# Terminierung_RS485_RJ45.net
KiCad netlist of a schematic drawn in EAGLE
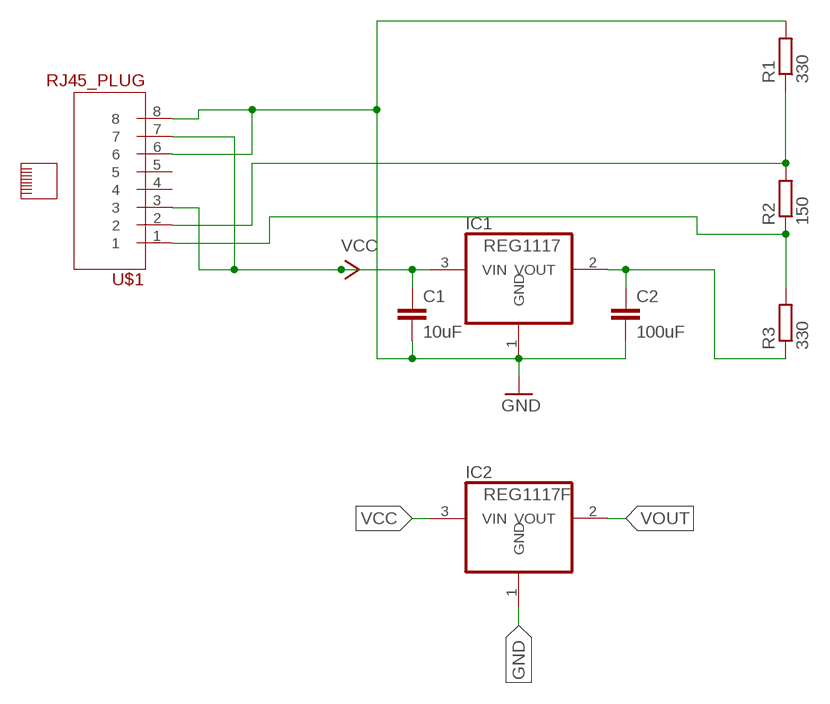
[diagram p0: schematic, sheet 1]

(export (version "E")
  (design (tool "Eeschema 10.0.6"))
  (components
    (comp (ref "C1")
      (value "10uF")
      (footprint "eagle-import:C0805K")
      (libsource (lib "eagle-import") (part "C-EUC0805K"))
    )
    (comp (ref "C2")
      (value "100uF")
      (footprint "eagle-import:C0805K")
      (libsource (lib "eagle-import") (part "C-EUC0805K"))
    )
    (comp (ref "IC1")
      (value "REG1117")
      (footprint "eagle-import:SOT223")
      (libsource (lib "eagle-import") (part "REG1117"))
    )
    (comp (ref "IC2")
      (value "REG1117F")
      (footprint "eagle-import:DD-3")
      (fields (field (name "MF") "TEXAS INSTRUMENTS") (field (name "MPN") "REG1117FAKTTT"))
      (libsource (lib "eagle-import") (part "REG1117F"))
    )
    (comp (ref "R1")
      (value "330")
      (footprint "eagle-import:R0805")
      (libsource (lib "eagle-import") (part "R-EU_R0805"))
    )
    (comp (ref "R2")
      (value "150")
      (footprint "eagle-import:R0805")
      (libsource (lib "eagle-import") (part "R-EU_R0805"))
    )
    (comp (ref "R3")
      (value "330")
      (footprint "eagle-import:R0805")
      (libsource (lib "eagle-import") (part "R-EU_R0805"))
    )
    (comp (ref "U$1")
      (value "RJ45_PLUG")
      (footprint "eagle-import:RJ45_PLUG")
      (libsource (lib "eagle-import") (part "RJ45_PLUG"))
    )
  )
  (nets
    (net (code "1") (name "GND") (class "Default")
      (node (ref "C1") (pin "2") (pinfunction "2_2") (pintype "passive"))
      (node (ref "C2") (pin "2") (pinfunction "2_2") (pintype "passive"))
      (node (ref "IC1") (pin "1") (pinfunction "GND_1") (pintype "power_in"))
      (node (ref "IC2") (pin "1") (pinfunction "GND_1") (pintype "power_in"))
      (node (ref "R1") (pin "2") (pinfunction "2_2") (pintype "passive"))
      (node (ref "U$1") (pin "6") (pinfunction "6_6") (pintype "bidirectional"))
      (node (ref "U$1") (pin "8") (pinfunction "8_8") (pintype "bidirectional"))
    )
    (net (code "2") (name "Net-(R1-Pad1)") (class "Default")
      (node (ref "R1") (pin "1") (pinfunction "1_1") (pintype "passive"))
      (node (ref "R2") (pin "2") (pinfunction "2_2") (pintype "passive"))
      (node (ref "U$1") (pin "2") (pinfunction "2_2") (pintype "bidirectional"))
    )
    (net (code "3") (name "Net-(R2-Pad1)") (class "Default")
      (node (ref "R2") (pin "1") (pinfunction "1_1") (pintype "passive"))
      (node (ref "R3") (pin "2") (pinfunction "2_2") (pintype "passive"))
      (node (ref "U$1") (pin "1") (pinfunction "1_1") (pintype "bidirectional"))
    )
    (net (code "4") (name "VCC") (class "Default")
      (node (ref "C1") (pin "1") (pinfunction "1_1") (pintype "passive"))
      (node (ref "IC1") (pin "3") (pinfunction "VIN_3") (pintype "input"))
      (node (ref "IC2") (pin "3") (pinfunction "VIN_3") (pintype "input"))
      (node (ref "U$1") (pin "3") (pinfunction "3_3") (pintype "bidirectional"))
      (node (ref "U$1") (pin "7") (pinfunction "7_7") (pintype "bidirectional"))
    )
    (net (code "5") (name "VOUT") (class "Default")
      (node (ref "C2") (pin "1") (pinfunction "1_1") (pintype "passive"))
      (node (ref "IC1") (pin "2") (pinfunction "VOUT_2") (pintype "output"))
      (node (ref "IC2") (pin "2") (pinfunction "VOUT_2") (pintype "output"))
      (node (ref "R3") (pin "1") (pinfunction "1_1") (pintype "passive"))
    )
    (net (code "6") (name "unconnected-(U$1-Pad4)") (class "Default")
      (node (ref "U$1") (pin "4") (pinfunction "4_4") (pintype "bidirectional"))
    )
    (net (code "7") (name "unconnected-(U$1-Pad5)") (class "Default")
      (node (ref "U$1") (pin "5") (pinfunction "5_5") (pintype "bidirectional"))
    )
  )
)
